# Trimble_Thunderbolt_Monitor_Shield_v1_1.net
KiCad netlist of a schematic drawn in EAGLE
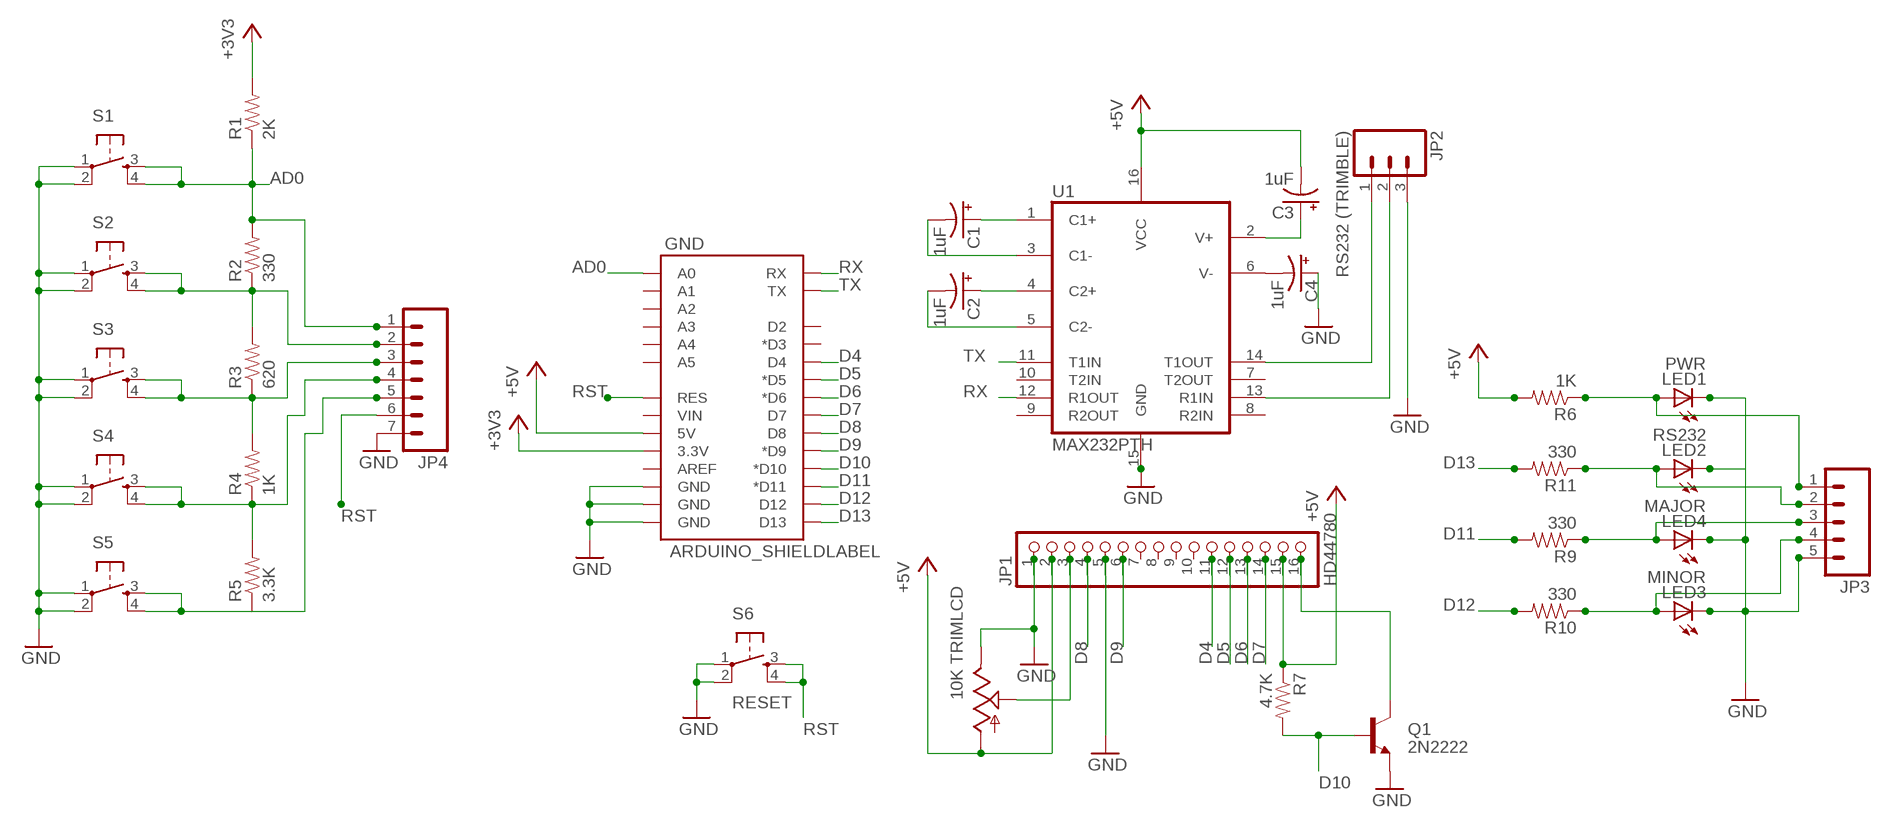
[diagram p0: schematic, sheet 1]

(export (version "E")
  (design (tool "Eeschema 10.0.6"))
  (components
    (comp (ref "C1")
      (value "1uF")
      (footprint "eagle-import:CPOL-RADIAL-10UF-25V")
      (libsource (lib "eagle-import") (part "CAP_POLPTH2"))
    )
    (comp (ref "C2")
      (value "1uF")
      (footprint "eagle-import:CPOL-RADIAL-10UF-25V")
      (libsource (lib "eagle-import") (part "CAP_POLPTH2"))
    )
    (comp (ref "C3")
      (value "1uF")
      (footprint "eagle-import:CPOL-RADIAL-10UF-25V")
      (libsource (lib "eagle-import") (part "CAP_POLPTH2"))
    )
    (comp (ref "C4")
      (value "1uF")
      (footprint "eagle-import:CPOL-RADIAL-10UF-25V")
      (libsource (lib "eagle-import") (part "CAP_POLPTH2"))
    )
    (comp (ref "GND")
      (value "ARDUINO_SHIELDLABEL")
      (footprint "eagle-import:DUEMILANOVE_SHIELD")
      (libsource (lib "eagle-import") (part "ARDUINO_SHIELDLABEL"))
    )
    (comp (ref "JP1")
      (value "HD44780")
      (footprint "eagle-import:1X16")
      (libsource (lib "eagle-import") (part "PINHD-1X16"))
    )
    (comp (ref "JP2")
      (value "RS232 (TRIMBLE)")
      (footprint "eagle-import:MOLEX-1X3")
      (libsource (lib "eagle-import") (part "M03POLAR"))
    )
    (comp (ref "JP3")
      (value "M05PTH")
      (footprint "eagle-import:1X05")
      (libsource (lib "eagle-import") (part "M05PTH"))
    )
    (comp (ref "JP4")
      (value "M07")
      (footprint "eagle-import:1X07")
      (libsource (lib "eagle-import") (part "M07"))
    )
    (comp (ref "LED1")
      (value "PWR")
      (footprint "eagle-import:LED5MM")
      (libsource (lib "eagle-import") (part "LED5MM"))
    )
    (comp (ref "LED2")
      (value "RS232")
      (footprint "eagle-import:LED5MM")
      (libsource (lib "eagle-import") (part "LED5MM"))
    )
    (comp (ref "LED3")
      (value "MINOR")
      (footprint "eagle-import:LED5MM")
      (libsource (lib "eagle-import") (part "LED5MM"))
    )
    (comp (ref "LED4")
      (value "MAJOR")
      (footprint "eagle-import:LED5MM")
      (libsource (lib "eagle-import") (part "LED5MM"))
    )
    (comp (ref "Q1")
      (value "2N2222")
      (footprint "eagle-import:TO-92-AMMO")
      (libsource (lib "eagle-import") (part "TRANSISTOR_NPNTO-92-AMMO"))
    )
    (comp (ref "R1")
      (value "2K")
      (footprint "eagle-import:AXIAL-0.3")
      (libsource (lib "eagle-import") (part "RESISTORAXIAL-0.3"))
    )
    (comp (ref "R2")
      (value "330")
      (footprint "eagle-import:AXIAL-0.3")
      (libsource (lib "eagle-import") (part "RESISTORAXIAL-0.3"))
    )
    (comp (ref "R3")
      (value "620")
      (footprint "eagle-import:AXIAL-0.3")
      (libsource (lib "eagle-import") (part "RESISTORAXIAL-0.3"))
    )
    (comp (ref "R4")
      (value "1K")
      (footprint "eagle-import:AXIAL-0.3")
      (libsource (lib "eagle-import") (part "RESISTORAXIAL-0.3"))
    )
    (comp (ref "R5")
      (value "3.3K")
      (footprint "eagle-import:AXIAL-0.3")
      (libsource (lib "eagle-import") (part "RESISTORAXIAL-0.3"))
    )
    (comp (ref "R6")
      (value "1K")
      (footprint "eagle-import:AXIAL-0.3")
      (libsource (lib "eagle-import") (part "RESISTORAXIAL-0.3"))
    )
    (comp (ref "R7")
      (value "4.7K")
      (footprint "eagle-import:AXIAL-0.3")
      (libsource (lib "eagle-import") (part "RESISTORAXIAL-0.3"))
    )
    (comp (ref "R9")
      (value "330")
      (footprint "eagle-import:AXIAL-0.3")
      (libsource (lib "eagle-import") (part "RESISTORAXIAL-0.3"))
    )
    (comp (ref "R10")
      (value "330")
      (footprint "eagle-import:AXIAL-0.3")
      (libsource (lib "eagle-import") (part "RESISTORAXIAL-0.3"))
    )
    (comp (ref "R11")
      (value "330")
      (footprint "eagle-import:AXIAL-0.3")
      (libsource (lib "eagle-import") (part "RESISTORAXIAL-0.3"))
    )
    (comp (ref "S1")
      (value "TAC_SWITCHPTH")
      (footprint "eagle-import:TACTILE-PTH")
      (libsource (lib "eagle-import") (part "TAC_SWITCHPTH"))
    )
    (comp (ref "S2")
      (value "TAC_SWITCHPTH")
      (footprint "eagle-import:TACTILE-PTH")
      (libsource (lib "eagle-import") (part "TAC_SWITCHPTH"))
    )
    (comp (ref "S3")
      (value "TAC_SWITCHPTH")
      (footprint "eagle-import:TACTILE-PTH")
      (libsource (lib "eagle-import") (part "TAC_SWITCHPTH"))
    )
    (comp (ref "S4")
      (value "TAC_SWITCHPTH")
      (footprint "eagle-import:TACTILE-PTH")
      (libsource (lib "eagle-import") (part "TAC_SWITCHPTH"))
    )
    (comp (ref "S5")
      (value "TAC_SWITCHPTH")
      (footprint "eagle-import:TACTILE-PTH")
      (libsource (lib "eagle-import") (part "TAC_SWITCHPTH"))
    )
    (comp (ref "S6")
      (value "RESET")
      (footprint "eagle-import:TACTILE-PTH")
      (libsource (lib "eagle-import") (part "TAC_SWITCHPTH"))
    )
    (comp (ref "TRIMLCD")
      (value "10K")
      (footprint "eagle-import:3362U")
      (libsource (lib "eagle-import") (part "POT100K_3362U"))
    )
    (comp (ref "U1")
      (value "MAX232PTH")
      (footprint "eagle-import:DIL16")
      (libsource (lib "eagle-import") (part "MAX232PTH"))
    )
  )
  (nets
    (net (code "1") (name "+3V3") (class "Default")
      (node (ref "GND") (pin "3.3V") (pinfunction "3.3V_3.3V") (pintype "bidirectional"))
      (node (ref "R1") (pin "P$2") (pinfunction "2_P$2") (pintype "passive"))
    )
    (net (code "2") (name "+5V") (class "Default")
      (node (ref "C3") (pin "2") (pinfunction "-_2") (pintype "passive"))
      (node (ref "GND") (pin "5V") (pinfunction "5V_5V") (pintype "bidirectional"))
      (node (ref "JP1") (pin "15") (pinfunction "15_15") (pintype "passive"))
      (node (ref "JP1") (pin "2") (pinfunction "2_2") (pintype "passive"))
      (node (ref "R6") (pin "P$2") (pinfunction "2_P$2") (pintype "passive"))
      (node (ref "R7") (pin "P$1") (pinfunction "1_P$1") (pintype "passive"))
      (node (ref "TRIMLCD") (pin "P$3") (pinfunction "A_P$3") (pintype "passive"))
      (node (ref "U1") (pin "16") (pinfunction "VCC_16") (pintype "bidirectional"))
    )
    (net (code "3") (name "/AD0") (class "Default")
      (node (ref "GND") (pin "A0") (pinfunction "A0_A0") (pintype "bidirectional"))
      (node (ref "JP4") (pin "1") (pinfunction "1_1") (pintype "passive"))
      (node (ref "R1") (pin "P$1") (pinfunction "1_P$1") (pintype "passive"))
      (node (ref "R2") (pin "P$2") (pinfunction "2_P$2") (pintype "passive"))
      (node (ref "S1") (pin "3") (pinfunction "3_3") (pintype "passive"))
      (node (ref "S1") (pin "4") (pinfunction "4_4") (pintype "passive"))
    )
    (net (code "4") (name "/D4") (class "Default")
      (node (ref "GND") (pin "D4") (pinfunction "D4_D4") (pintype "bidirectional"))
      (node (ref "JP1") (pin "11") (pinfunction "11_11") (pintype "passive"))
    )
    (net (code "5") (name "/D5") (class "Default")
      (node (ref "GND") (pin "D5") (pinfunction "*D5_D5") (pintype "bidirectional"))
      (node (ref "JP1") (pin "12") (pinfunction "12_12") (pintype "passive"))
    )
    (net (code "6") (name "/D6") (class "Default")
      (node (ref "GND") (pin "D6") (pinfunction "*D6_D6") (pintype "bidirectional"))
      (node (ref "JP1") (pin "13") (pinfunction "13_13") (pintype "passive"))
    )
    (net (code "7") (name "/D7") (class "Default")
      (node (ref "GND") (pin "D7") (pinfunction "D7_D7") (pintype "bidirectional"))
      (node (ref "JP1") (pin "14") (pinfunction "14_14") (pintype "passive"))
    )
    (net (code "8") (name "/D8") (class "Default")
      (node (ref "GND") (pin "D8") (pinfunction "D8_D8") (pintype "bidirectional"))
      (node (ref "JP1") (pin "4") (pinfunction "4_4") (pintype "passive"))
    )
    (net (code "9") (name "/D9") (class "Default")
      (node (ref "GND") (pin "D9") (pinfunction "*D9_D9") (pintype "bidirectional"))
      (node (ref "JP1") (pin "6") (pinfunction "6_6") (pintype "passive"))
    )
    (net (code "10") (name "/D10") (class "Default")
      (node (ref "GND") (pin "D10") (pinfunction "*D10_D10") (pintype "bidirectional"))
      (node (ref "Q1") (pin "2") (pinfunction "B_2") (pintype "passive"))
      (node (ref "R7") (pin "P$2") (pinfunction "2_P$2") (pintype "passive"))
    )
    (net (code "11") (name "/D11") (class "Default")
      (node (ref "GND") (pin "D11") (pinfunction "*D11_D11") (pintype "bidirectional"))
      (node (ref "R9") (pin "P$2") (pinfunction "2_P$2") (pintype "passive"))
    )
    (net (code "12") (name "/D12") (class "Default")
      (node (ref "GND") (pin "D12") (pinfunction "D12_D12") (pintype "bidirectional"))
      (node (ref "R10") (pin "P$2") (pinfunction "2_P$2") (pintype "passive"))
    )
    (net (code "13") (name "/D13") (class "Default")
      (node (ref "GND") (pin "D13") (pinfunction "D13_D13") (pintype "bidirectional"))
      (node (ref "R11") (pin "P$2") (pinfunction "2_P$2") (pintype "passive"))
    )
    (net (code "14") (name "/RST") (class "Default")
      (node (ref "GND") (pin "RES") (pinfunction "RES_RES") (pintype "bidirectional"))
      (node (ref "JP4") (pin "6") (pinfunction "6_6") (pintype "passive"))
      (node (ref "S6") (pin "3") (pinfunction "3_3") (pintype "passive"))
      (node (ref "S6") (pin "4") (pinfunction "4_4") (pintype "passive"))
    )
    (net (code "15") (name "/RX") (class "Default")
      (node (ref "GND") (pin "RX") (pinfunction "RX_RX") (pintype "bidirectional"))
      (node (ref "U1") (pin "12") (pinfunction "R1OUT_12") (pintype "output"))
    )
    (net (code "16") (name "/TX") (class "Default")
      (node (ref "GND") (pin "TX") (pinfunction "TX_TX") (pintype "bidirectional"))
      (node (ref "U1") (pin "11") (pinfunction "T1IN_11") (pintype "input"))
    )
    (net (code "17") (name "GND") (class "Default")
      (node (ref "C4") (pin "1") (pinfunction "+_1") (pintype "passive"))
      (node (ref "GND") (pin "GND@0") (pinfunction "GND_GND@0") (pintype "bidirectional"))
      (node (ref "GND") (pin "GND@1") (pinfunction "GND_GND@1") (pintype "bidirectional"))
      (node (ref "GND") (pin "GND@2") (pinfunction "GND_GND@2") (pintype "bidirectional"))
      (node (ref "JP1") (pin "1") (pinfunction "1_1") (pintype "passive"))
      (node (ref "JP1") (pin "5") (pinfunction "5_5") (pintype "passive"))
      (node (ref "JP2") (pin "3") (pinfunction "3_3") (pintype "passive"))
      (node (ref "JP3") (pin "5") (pinfunction "5_5") (pintype "passive"))
      (node (ref "JP4") (pin "7") (pinfunction "7_7") (pintype "passive"))
      (node (ref "LED1") (pin "K") (pinfunction "C_K") (pintype "passive"))
      (node (ref "LED2") (pin "K") (pinfunction "C_K") (pintype "passive"))
      (node (ref "LED3") (pin "K") (pinfunction "C_K") (pintype "passive"))
      (node (ref "LED4") (pin "K") (pinfunction "C_K") (pintype "passive"))
      (node (ref "Q1") (pin "1") (pinfunction "E_1") (pintype "passive"))
      (node (ref "S1") (pin "1") (pinfunction "1_1") (pintype "passive"))
      (node (ref "S1") (pin "2") (pinfunction "2_2") (pintype "passive"))
      (node (ref "S2") (pin "1") (pinfunction "1_1") (pintype "passive"))
      (node (ref "S2") (pin "2") (pinfunction "2_2") (pintype "passive"))
      (node (ref "S3") (pin "1") (pinfunction "1_1") (pintype "passive"))
      (node (ref "S3") (pin "2") (pinfunction "2_2") (pintype "passive"))
      (node (ref "S4") (pin "1") (pinfunction "1_1") (pintype "passive"))
      (node (ref "S4") (pin "2") (pinfunction "2_2") (pintype "passive"))
      (node (ref "S5") (pin "1") (pinfunction "1_1") (pintype "passive"))
      (node (ref "S5") (pin "2") (pinfunction "2_2") (pintype "passive"))
      (node (ref "S6") (pin "1") (pinfunction "1_1") (pintype "passive"))
      (node (ref "S6") (pin "2") (pinfunction "2_2") (pintype "passive"))
      (node (ref "TRIMLCD") (pin "P$1") (pinfunction "E_P$1") (pintype "passive"))
      (node (ref "U1") (pin "15") (pinfunction "GND_15") (pintype "bidirectional"))
    )
    (net (code "18") (name "Net-(C1-+)") (class "Default")
      (node (ref "C1") (pin "1") (pinfunction "+_1") (pintype "passive"))
      (node (ref "U1") (pin "1") (pinfunction "C1+_1") (pintype "bidirectional"))
    )
    (net (code "19") (name "Net-(C1--)") (class "Default")
      (node (ref "C1") (pin "2") (pinfunction "-_2") (pintype "passive"))
      (node (ref "U1") (pin "3") (pinfunction "C1-_3") (pintype "bidirectional"))
    )
    (net (code "20") (name "Net-(C2-+)") (class "Default")
      (node (ref "C2") (pin "1") (pinfunction "+_1") (pintype "passive"))
      (node (ref "U1") (pin "4") (pinfunction "C2+_4") (pintype "bidirectional"))
    )
    (net (code "21") (name "Net-(C2--)") (class "Default")
      (node (ref "C2") (pin "2") (pinfunction "-_2") (pintype "passive"))
      (node (ref "U1") (pin "5") (pinfunction "C2-_5") (pintype "bidirectional"))
    )
    (net (code "22") (name "Net-(C3-+)") (class "Default")
      (node (ref "C3") (pin "1") (pinfunction "+_1") (pintype "passive"))
      (node (ref "U1") (pin "2") (pinfunction "V+_2") (pintype "bidirectional"))
    )
    (net (code "23") (name "Net-(C4--)") (class "Default")
      (node (ref "C4") (pin "2") (pinfunction "-_2") (pintype "passive"))
      (node (ref "U1") (pin "6") (pinfunction "V-_6") (pintype "bidirectional"))
    )
    (net (code "24") (name "Net-(Q1-C)") (class "Default")
      (node (ref "JP1") (pin "16") (pinfunction "16_16") (pintype "passive"))
      (node (ref "Q1") (pin "3") (pinfunction "C_3") (pintype "passive"))
    )
    (net (code "25") (name "Net-(R2-1)") (class "Default")
      (node (ref "JP4") (pin "2") (pinfunction "2_2") (pintype "passive"))
      (node (ref "R2") (pin "P$1") (pinfunction "1_P$1") (pintype "passive"))
      (node (ref "R3") (pin "P$2") (pinfunction "2_P$2") (pintype "passive"))
      (node (ref "S2") (pin "3") (pinfunction "3_3") (pintype "passive"))
      (node (ref "S2") (pin "4") (pinfunction "4_4") (pintype "passive"))
    )
    (net (code "26") (name "Net-(R3-1)") (class "Default")
      (node (ref "JP4") (pin "3") (pinfunction "3_3") (pintype "passive"))
      (node (ref "R3") (pin "P$1") (pinfunction "1_P$1") (pintype "passive"))
      (node (ref "R4") (pin "P$2") (pinfunction "2_P$2") (pintype "passive"))
      (node (ref "S3") (pin "3") (pinfunction "3_3") (pintype "passive"))
      (node (ref "S3") (pin "4") (pinfunction "4_4") (pintype "passive"))
    )
    (net (code "27") (name "Net-(R4-1)") (class "Default")
      (node (ref "JP4") (pin "4") (pinfunction "4_4") (pintype "passive"))
      (node (ref "R4") (pin "P$1") (pinfunction "1_P$1") (pintype "passive"))
      (node (ref "R5") (pin "P$2") (pinfunction "2_P$2") (pintype "passive"))
      (node (ref "S4") (pin "3") (pinfunction "3_3") (pintype "passive"))
      (node (ref "S4") (pin "4") (pinfunction "4_4") (pintype "passive"))
    )
    (net (code "28") (name "Net-(R5-1)") (class "Default")
      (node (ref "JP4") (pin "5") (pinfunction "5_5") (pintype "passive"))
      (node (ref "R5") (pin "P$1") (pinfunction "1_P$1") (pintype "passive"))
      (node (ref "S5") (pin "3") (pinfunction "3_3") (pintype "passive"))
      (node (ref "S5") (pin "4") (pinfunction "4_4") (pintype "passive"))
    )
    (net (code "29") (name "Net-(R6-1)") (class "Default")
      (node (ref "JP3") (pin "1") (pinfunction "1_1") (pintype "passive"))
      (node (ref "LED1") (pin "A") (pinfunction "A_A") (pintype "passive"))
      (node (ref "R6") (pin "P$1") (pinfunction "1_P$1") (pintype "passive"))
    )
    (net (code "30") (name "Net-(R9-1)") (class "Default")
      (node (ref "JP3") (pin "3") (pinfunction "3_3") (pintype "passive"))
      (node (ref "LED4") (pin "A") (pinfunction "A_A") (pintype "passive"))
      (node (ref "R9") (pin "P$1") (pinfunction "1_P$1") (pintype "passive"))
    )
    (net (code "31") (name "Net-(R10-1)") (class "Default")
      (node (ref "JP3") (pin "4") (pinfunction "4_4") (pintype "passive"))
      (node (ref "LED3") (pin "A") (pinfunction "A_A") (pintype "passive"))
      (node (ref "R10") (pin "P$1") (pinfunction "1_P$1") (pintype "passive"))
    )
    (net (code "32") (name "Net-(R11-1)") (class "Default")
      (node (ref "JP3") (pin "2") (pinfunction "2_2") (pintype "passive"))
      (node (ref "LED2") (pin "A") (pinfunction "A_A") (pintype "passive"))
      (node (ref "R11") (pin "P$1") (pinfunction "1_P$1") (pintype "passive"))
    )
    (net (code "33") (name "Net-(TRIMLCD-S)") (class "Default")
      (node (ref "JP1") (pin "3") (pinfunction "3_3") (pintype "passive"))
      (node (ref "TRIMLCD") (pin "P$2") (pinfunction "S_P$2") (pintype "passive"))
    )
    (net (code "34") (name "Net-(U1-R1IN)") (class "Default")
      (node (ref "JP2") (pin "2") (pinfunction "2_2") (pintype "passive"))
      (node (ref "U1") (pin "13") (pinfunction "R1IN_13") (pintype "input"))
    )
    (net (code "35") (name "Net-(U1-T1OUT)") (class "Default")
      (node (ref "JP2") (pin "1") (pinfunction "1_1") (pintype "passive"))
      (node (ref "U1") (pin "14") (pinfunction "T1OUT_14") (pintype "output"))
    )
    (net (code "36") (name "unconnected-(GND-*D3-PadD3)") (class "Default")
      (node (ref "GND") (pin "D3") (pinfunction "*D3_D3") (pintype "bidirectional"))
    )
    (net (code "37") (name "unconnected-(GND-PadA1)") (class "Default")
      (node (ref "GND") (pin "A1") (pinfunction "A1_A1") (pintype "bidirectional"))
    )
    (net (code "38") (name "unconnected-(GND-PadA2)") (class "Default")
      (node (ref "GND") (pin "A2") (pinfunction "A2_A2") (pintype "bidirectional"))
    )
    (net (code "39") (name "unconnected-(GND-PadA3)") (class "Default")
      (node (ref "GND") (pin "A3") (pinfunction "A3_A3") (pintype "bidirectional"))
    )
    (net (code "40") (name "unconnected-(GND-PadA4)") (class "Default")
      (node (ref "GND") (pin "A4") (pinfunction "A4_A4") (pintype "bidirectional"))
    )
    (net (code "41") (name "unconnected-(GND-PadA5)") (class "Default")
      (node (ref "GND") (pin "A5") (pinfunction "A5_A5") (pintype "bidirectional"))
    )
    (net (code "42") (name "unconnected-(GND-PadAREF)") (class "Default")
      (node (ref "GND") (pin "AREF") (pinfunction "AREF_AREF") (pintype "bidirectional"))
    )
    (net (code "43") (name "unconnected-(GND-PadD2)") (class "Default")
      (node (ref "GND") (pin "D2") (pinfunction "D2_D2") (pintype "bidirectional"))
    )
    (net (code "44") (name "unconnected-(GND-PadVIN)") (class "Default")
      (node (ref "GND") (pin "VIN") (pinfunction "VIN_VIN") (pintype "bidirectional"))
    )
    (net (code "45") (name "unconnected-(JP1-Pad7)") (class "Default")
      (node (ref "JP1") (pin "7") (pinfunction "7_7") (pintype "passive"))
    )
    (net (code "46") (name "unconnected-(JP1-Pad8)") (class "Default")
      (node (ref "JP1") (pin "8") (pinfunction "8_8") (pintype "passive"))
    )
    (net (code "47") (name "unconnected-(JP1-Pad9)") (class "Default")
      (node (ref "JP1") (pin "9") (pinfunction "9_9") (pintype "passive"))
    )
    (net (code "48") (name "unconnected-(JP1-Pad10)") (class "Default")
      (node (ref "JP1") (pin "10") (pinfunction "10_10") (pintype "passive"))
    )
    (net (code "49") (name "unconnected-(U1-R2IN-Pad8)") (class "Default")
      (node (ref "U1") (pin "8") (pinfunction "R2IN_8") (pintype "input"))
    )
    (net (code "50") (name "unconnected-(U1-R2OUT-Pad9)") (class "Default")
      (node (ref "U1") (pin "9") (pinfunction "R2OUT_9") (pintype "output"))
    )
    (net (code "51") (name "unconnected-(U1-T2IN-Pad10)") (class "Default")
      (node (ref "U1") (pin "10") (pinfunction "T2IN_10") (pintype "input"))
    )
    (net (code "52") (name "unconnected-(U1-T2OUT-Pad7)") (class "Default")
      (node (ref "U1") (pin "7") (pinfunction "T2OUT_7") (pintype "output"))
    )
  )
)
